# L6472V1.net
KiCad netlist of a schematic drawn in EAGLE
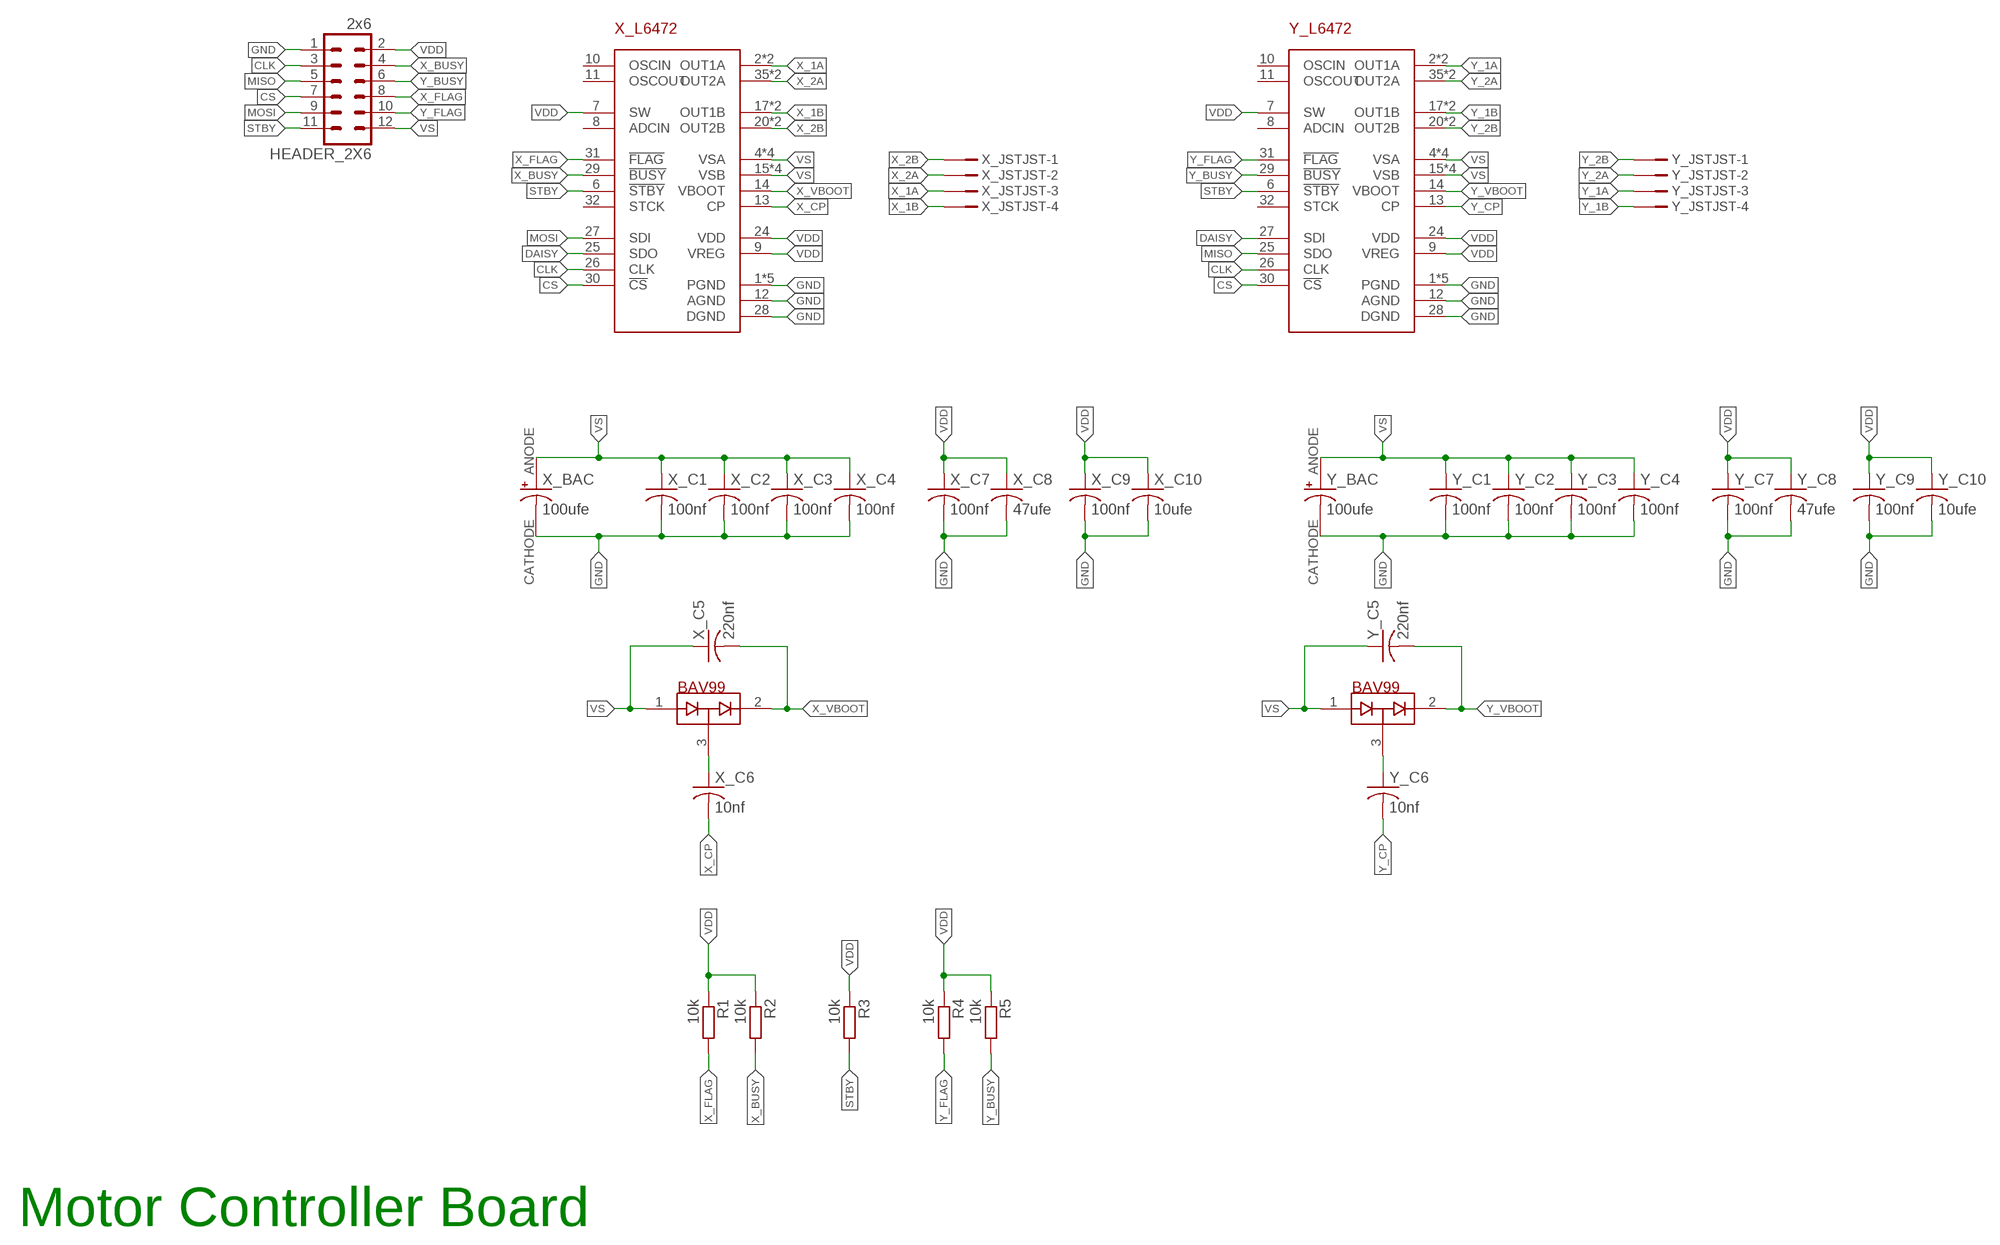
[diagram p0: schematic, sheet 1]

(export (version "E")
  (design (tool "Eeschema 10.0.6"))
  (components
    (comp (ref "HEADER_2X6")
      (value "2x6")
      (footprint "eagle-import:MA06-2")
      (libsource (lib "eagle-import") (part "MA06-2"))
    )
    (comp (ref "R1")
      (value "10k")
      (footprint "eagle-import:M1206")
      (libsource (lib "eagle-import") (part "R-EU_M1206"))
    )
    (comp (ref "R2")
      (value "10k")
      (footprint "eagle-import:M1206")
      (libsource (lib "eagle-import") (part "R-EU_M1206"))
    )
    (comp (ref "R3")
      (value "10k")
      (footprint "eagle-import:M1206")
      (libsource (lib "eagle-import") (part "R-EU_M1206"))
    )
    (comp (ref "R4")
      (value "10k")
      (footprint "eagle-import:M1206")
      (libsource (lib "eagle-import") (part "R-EU_M1206"))
    )
    (comp (ref "R5")
      (value "10k")
      (footprint "eagle-import:M1206")
      (libsource (lib "eagle-import") (part "R-EU_M1206"))
    )
    (comp (ref "X_BAC")
      (value "100ufe")
      (footprint "eagle-import:EEE1AA101WR")
      (libsource (lib "eagle-import") (part "EEE-1AA101WR"))
    )
    (comp (ref "X_BAV99")
      (value "BAV99")
      (footprint "eagle-import:SOT23_CPL")
      (libsource (lib "eagle-import") (part "BAV99"))
    )
    (comp (ref "X_C1")
      (value "100nf")
      (footprint "eagle-import:C1206")
      (libsource (lib "eagle-import") (part "C-USC1206"))
    )
    (comp (ref "X_C2")
      (value "100nf")
      (footprint "eagle-import:C1206")
      (libsource (lib "eagle-import") (part "C-USC1206"))
    )
    (comp (ref "X_C3")
      (value "100nf")
      (footprint "eagle-import:C1206")
      (libsource (lib "eagle-import") (part "C-USC1206"))
    )
    (comp (ref "X_C4")
      (value "100nf")
      (footprint "eagle-import:C1206")
      (libsource (lib "eagle-import") (part "C-USC1206"))
    )
    (comp (ref "X_C5")
      (value "220nf")
      (footprint "eagle-import:C1206")
      (libsource (lib "eagle-import") (part "C-USC1206"))
    )
    (comp (ref "X_C6")
      (value "10nf")
      (footprint "eagle-import:C1206")
      (libsource (lib "eagle-import") (part "C-USC1206"))
    )
    (comp (ref "X_C7")
      (value "100nf")
      (footprint "eagle-import:C1206")
      (libsource (lib "eagle-import") (part "C-USC1206"))
    )
    (comp (ref "X_C8")
      (value "47ufe")
      (footprint "eagle-import:C1206")
      (libsource (lib "eagle-import") (part "C-USC1206"))
    )
    (comp (ref "X_C9")
      (value "100nf")
      (footprint "eagle-import:C1206")
      (libsource (lib "eagle-import") (part "C-USC1206"))
    )
    (comp (ref "X_C10")
      (value "10ufe")
      (footprint "eagle-import:C1206")
      (libsource (lib "eagle-import") (part "C-USC1206"))
    )
    (comp (ref "X_JST")
      (value "JST")
      (footprint "eagle-import:JST-4")
      (libsource (lib "eagle-import") (part "JST"))
    )
    (comp (ref "X_L6472")
      (value "L6472")
      (footprint "eagle-import:PSO36")
      (libsource (lib "eagle-import") (part "L6472"))
    )
    (comp (ref "Y_BAC")
      (value "100ufe")
      (footprint "eagle-import:EEE1AA101WR")
      (libsource (lib "eagle-import") (part "EEE-1AA101WR"))
    )
    (comp (ref "Y_BAV99")
      (value "BAV99")
      (footprint "eagle-import:SOT23_CPL")
      (libsource (lib "eagle-import") (part "BAV99"))
    )
    (comp (ref "Y_C1")
      (value "100nf")
      (footprint "eagle-import:C1206")
      (libsource (lib "eagle-import") (part "C-USC1206"))
    )
    (comp (ref "Y_C2")
      (value "100nf")
      (footprint "eagle-import:C1206")
      (libsource (lib "eagle-import") (part "C-USC1206"))
    )
    (comp (ref "Y_C3")
      (value "100nf")
      (footprint "eagle-import:C1206")
      (libsource (lib "eagle-import") (part "C-USC1206"))
    )
    (comp (ref "Y_C4")
      (value "100nf")
      (footprint "eagle-import:C1206")
      (libsource (lib "eagle-import") (part "C-USC1206"))
    )
    (comp (ref "Y_C5")
      (value "220nf")
      (footprint "eagle-import:C1206")
      (libsource (lib "eagle-import") (part "C-USC1206"))
    )
    (comp (ref "Y_C6")
      (value "10nf")
      (footprint "eagle-import:C1206")
      (libsource (lib "eagle-import") (part "C-USC1206"))
    )
    (comp (ref "Y_C7")
      (value "100nf")
      (footprint "eagle-import:C1206")
      (libsource (lib "eagle-import") (part "C-USC1206"))
    )
    (comp (ref "Y_C8")
      (value "47ufe")
      (footprint "eagle-import:C1206")
      (libsource (lib "eagle-import") (part "C-USC1206"))
    )
    (comp (ref "Y_C9")
      (value "100nf")
      (footprint "eagle-import:C1206")
      (libsource (lib "eagle-import") (part "C-USC1206"))
    )
    (comp (ref "Y_C10")
      (value "10ufe")
      (footprint "eagle-import:C1206")
      (libsource (lib "eagle-import") (part "C-USC1206"))
    )
    (comp (ref "Y_JST")
      (value "JST")
      (footprint "eagle-import:JST-4")
      (libsource (lib "eagle-import") (part "JST"))
    )
    (comp (ref "Y_L6472")
      (value "L6472")
      (footprint "eagle-import:PSO36")
      (libsource (lib "eagle-import") (part "L6472"))
    )
  )
  (nets
    (net (code "1") (name "CLK") (class "Default")
      (node (ref "HEADER_2X6") (pin "3") (pinfunction "3_3") (pintype "passive"))
      (node (ref "X_L6472") (pin "26") (pinfunction "CLK_26") (pintype "bidirectional"))
      (node (ref "Y_L6472") (pin "26") (pinfunction "CLK_26") (pintype "bidirectional"))
    )
    (net (code "2") (name "CS") (class "Default")
      (node (ref "HEADER_2X6") (pin "7") (pinfunction "7_7") (pintype "passive"))
      (node (ref "X_L6472") (pin "30") (pinfunction "~{CS}_30") (pintype "bidirectional"))
      (node (ref "Y_L6472") (pin "30") (pinfunction "~{CS}_30") (pintype "bidirectional"))
    )
    (net (code "3") (name "DAISY") (class "Default")
      (node (ref "X_L6472") (pin "25") (pinfunction "SDO_25") (pintype "bidirectional"))
      (node (ref "Y_L6472") (pin "27") (pinfunction "SDI_27") (pintype "bidirectional"))
    )
    (net (code "4") (name "GND") (class "Default")
      (node (ref "HEADER_2X6") (pin "1") (pinfunction "1_1") (pintype "passive"))
      (node (ref "X_BAC") (pin "CATHODE") (pinfunction "-_CATHODE") (pintype "passive"))
      (node (ref "X_C1") (pin "2") (pinfunction "2_2") (pintype "passive"))
      (node (ref "X_C10") (pin "2") (pinfunction "2_2") (pintype "passive"))
      (node (ref "X_C2") (pin "2") (pinfunction "2_2") (pintype "passive"))
      (node (ref "X_C3") (pin "2") (pinfunction "2_2") (pintype "passive"))
      (node (ref "X_C4") (pin "2") (pinfunction "2_2") (pintype "passive"))
      (node (ref "X_C7") (pin "2") (pinfunction "2_2") (pintype "passive"))
      (node (ref "X_C8") (pin "2") (pinfunction "2_2") (pintype "passive"))
      (node (ref "X_C9") (pin "2") (pinfunction "2_2") (pintype "passive"))
      (node (ref "X_L6472") (pin "1") (pinfunction "PGND_1") (pintype "bidirectional"))
      (node (ref "X_L6472") (pin "12") (pinfunction "AGND_12") (pintype "bidirectional"))
      (node (ref "X_L6472") (pin "19") (pinfunction "PGND_19") (pintype "bidirectional"))
      (node (ref "X_L6472") (pin "28") (pinfunction "DGND_28") (pintype "bidirectional"))
      (node (ref "X_L6472") (pin "M@1") (pinfunction "PGND_M@1") (pintype "bidirectional"))
      (node (ref "X_L6472") (pin "M@2") (pinfunction "PGND_M@2") (pintype "bidirectional"))
      (node (ref "X_L6472") (pin "M@3") (pinfunction "PGND_M@3") (pintype "bidirectional"))
      (node (ref "Y_BAC") (pin "CATHODE") (pinfunction "-_CATHODE") (pintype "passive"))
      (node (ref "Y_C1") (pin "2") (pinfunction "2_2") (pintype "passive"))
      (node (ref "Y_C10") (pin "2") (pinfunction "2_2") (pintype "passive"))
      (node (ref "Y_C2") (pin "2") (pinfunction "2_2") (pintype "passive"))
      (node (ref "Y_C3") (pin "2") (pinfunction "2_2") (pintype "passive"))
      (node (ref "Y_C4") (pin "2") (pinfunction "2_2") (pintype "passive"))
      (node (ref "Y_C7") (pin "2") (pinfunction "2_2") (pintype "passive"))
      (node (ref "Y_C8") (pin "2") (pinfunction "2_2") (pintype "passive"))
      (node (ref "Y_C9") (pin "2") (pinfunction "2_2") (pintype "passive"))
      (node (ref "Y_L6472") (pin "1") (pinfunction "PGND_1") (pintype "bidirectional"))
      (node (ref "Y_L6472") (pin "12") (pinfunction "AGND_12") (pintype "bidirectional"))
      (node (ref "Y_L6472") (pin "19") (pinfunction "PGND_19") (pintype "bidirectional"))
      (node (ref "Y_L6472") (pin "28") (pinfunction "DGND_28") (pintype "bidirectional"))
      (node (ref "Y_L6472") (pin "M@1") (pinfunction "PGND_M@1") (pintype "bidirectional"))
      (node (ref "Y_L6472") (pin "M@2") (pinfunction "PGND_M@2") (pintype "bidirectional"))
      (node (ref "Y_L6472") (pin "M@3") (pinfunction "PGND_M@3") (pintype "bidirectional"))
    )
    (net (code "5") (name "MISO") (class "Default")
      (node (ref "HEADER_2X6") (pin "5") (pinfunction "5_5") (pintype "passive"))
      (node (ref "Y_L6472") (pin "25") (pinfunction "SDO_25") (pintype "bidirectional"))
    )
    (net (code "6") (name "MOSI") (class "Default")
      (node (ref "HEADER_2X6") (pin "9") (pinfunction "9_9") (pintype "passive"))
      (node (ref "X_L6472") (pin "27") (pinfunction "SDI_27") (pintype "bidirectional"))
    )
    (net (code "7") (name "Net-(X_BAV99-COM)") (class "Default")
      (node (ref "X_BAV99") (pin "3") (pinfunction "COM_3") (pintype "bidirectional"))
      (node (ref "X_C6") (pin "1") (pinfunction "1_1") (pintype "passive"))
    )
    (net (code "8") (name "Net-(Y_BAV99-COM)") (class "Default")
      (node (ref "Y_BAV99") (pin "3") (pinfunction "COM_3") (pintype "bidirectional"))
      (node (ref "Y_C6") (pin "1") (pinfunction "1_1") (pintype "passive"))
    )
    (net (code "9") (name "STBY") (class "Default")
      (node (ref "HEADER_2X6") (pin "11") (pinfunction "11_11") (pintype "passive"))
      (node (ref "R3") (pin "2") (pinfunction "2_2") (pintype "passive"))
      (node (ref "X_L6472") (pin "6") (pinfunction "~{STBY}_6") (pintype "bidirectional"))
      (node (ref "Y_L6472") (pin "6") (pinfunction "~{STBY}_6") (pintype "bidirectional"))
    )
    (net (code "10") (name "VDD") (class "Default")
      (node (ref "HEADER_2X6") (pin "2") (pinfunction "2_2") (pintype "passive"))
      (node (ref "R1") (pin "1") (pinfunction "1_1") (pintype "passive"))
      (node (ref "R2") (pin "1") (pinfunction "1_1") (pintype "passive"))
      (node (ref "R3") (pin "1") (pinfunction "1_1") (pintype "passive"))
      (node (ref "R4") (pin "1") (pinfunction "1_1") (pintype "passive"))
      (node (ref "R5") (pin "1") (pinfunction "1_1") (pintype "passive"))
      (node (ref "X_C10") (pin "1") (pinfunction "1_1") (pintype "passive"))
      (node (ref "X_C7") (pin "1") (pinfunction "1_1") (pintype "passive"))
      (node (ref "X_C8") (pin "1") (pinfunction "1_1") (pintype "passive"))
      (node (ref "X_C9") (pin "1") (pinfunction "1_1") (pintype "passive"))
      (node (ref "X_L6472") (pin "24") (pinfunction "VDD_24") (pintype "bidirectional"))
      (node (ref "X_L6472") (pin "7") (pinfunction "SW_7") (pintype "bidirectional"))
      (node (ref "X_L6472") (pin "9") (pinfunction "VREG_9") (pintype "bidirectional"))
      (node (ref "Y_C10") (pin "1") (pinfunction "1_1") (pintype "passive"))
      (node (ref "Y_C7") (pin "1") (pinfunction "1_1") (pintype "passive"))
      (node (ref "Y_C8") (pin "1") (pinfunction "1_1") (pintype "passive"))
      (node (ref "Y_C9") (pin "1") (pinfunction "1_1") (pintype "passive"))
      (node (ref "Y_L6472") (pin "24") (pinfunction "VDD_24") (pintype "bidirectional"))
      (node (ref "Y_L6472") (pin "7") (pinfunction "SW_7") (pintype "bidirectional"))
      (node (ref "Y_L6472") (pin "9") (pinfunction "VREG_9") (pintype "bidirectional"))
    )
    (net (code "11") (name "VS") (class "Default")
      (node (ref "HEADER_2X6") (pin "12") (pinfunction "12_12") (pintype "passive"))
      (node (ref "X_BAC") (pin "ANODE") (pinfunction "+_ANODE") (pintype "passive"))
      (node (ref "X_BAV99") (pin "1") (pinfunction "A1_1") (pintype "bidirectional"))
      (node (ref "X_C1") (pin "1") (pinfunction "1_1") (pintype "passive"))
      (node (ref "X_C2") (pin "1") (pinfunction "1_1") (pintype "passive"))
      (node (ref "X_C3") (pin "1") (pinfunction "1_1") (pintype "passive"))
      (node (ref "X_C4") (pin "1") (pinfunction "1_1") (pintype "passive"))
      (node (ref "X_C5") (pin "1") (pinfunction "1_1") (pintype "passive"))
      (node (ref "X_L6472") (pin "15") (pinfunction "VSB_15") (pintype "bidirectional"))
      (node (ref "X_L6472") (pin "16") (pinfunction "VSB_16") (pintype "bidirectional"))
      (node (ref "X_L6472") (pin "22") (pinfunction "VSB_22") (pintype "bidirectional"))
      (node (ref "X_L6472") (pin "23") (pinfunction "VSB_23") (pintype "bidirectional"))
      (node (ref "X_L6472") (pin "33") (pinfunction "VSA_33") (pintype "bidirectional"))
      (node (ref "X_L6472") (pin "34") (pinfunction "VSA_34") (pintype "bidirectional"))
      (node (ref "X_L6472") (pin "4") (pinfunction "VSA_4") (pintype "bidirectional"))
      (node (ref "X_L6472") (pin "5") (pinfunction "VSA_5") (pintype "bidirectional"))
      (node (ref "Y_BAC") (pin "ANODE") (pinfunction "+_ANODE") (pintype "passive"))
      (node (ref "Y_BAV99") (pin "1") (pinfunction "A1_1") (pintype "bidirectional"))
      (node (ref "Y_C1") (pin "1") (pinfunction "1_1") (pintype "passive"))
      (node (ref "Y_C2") (pin "1") (pinfunction "1_1") (pintype "passive"))
      (node (ref "Y_C3") (pin "1") (pinfunction "1_1") (pintype "passive"))
      (node (ref "Y_C4") (pin "1") (pinfunction "1_1") (pintype "passive"))
      (node (ref "Y_C5") (pin "1") (pinfunction "1_1") (pintype "passive"))
      (node (ref "Y_L6472") (pin "15") (pinfunction "VSB_15") (pintype "bidirectional"))
      (node (ref "Y_L6472") (pin "16") (pinfunction "VSB_16") (pintype "bidirectional"))
      (node (ref "Y_L6472") (pin "22") (pinfunction "VSB_22") (pintype "bidirectional"))
      (node (ref "Y_L6472") (pin "23") (pinfunction "VSB_23") (pintype "bidirectional"))
      (node (ref "Y_L6472") (pin "33") (pinfunction "VSA_33") (pintype "bidirectional"))
      (node (ref "Y_L6472") (pin "34") (pinfunction "VSA_34") (pintype "bidirectional"))
      (node (ref "Y_L6472") (pin "4") (pinfunction "VSA_4") (pintype "bidirectional"))
      (node (ref "Y_L6472") (pin "5") (pinfunction "VSA_5") (pintype "bidirectional"))
    )
    (net (code "12") (name "X_1A") (class "Default")
      (node (ref "X_JST") (pin "P2") (pinfunction "1_P2") (pintype "passive"))
      (node (ref "X_L6472") (pin "2") (pinfunction "OUT1A_2") (pintype "bidirectional"))
      (node (ref "X_L6472") (pin "3") (pinfunction "OUT1A_3") (pintype "bidirectional"))
    )
    (net (code "13") (name "X_1B") (class "Default")
      (node (ref "X_JST") (pin "P3") (pinfunction "1_P3") (pintype "passive"))
      (node (ref "X_L6472") (pin "17") (pinfunction "OUT1B_17") (pintype "bidirectional"))
      (node (ref "X_L6472") (pin "18") (pinfunction "OUT1B_18") (pintype "bidirectional"))
    )
    (net (code "14") (name "X_2A") (class "Default")
      (node (ref "X_JST") (pin "P1") (pinfunction "1_P1") (pintype "passive"))
      (node (ref "X_L6472") (pin "35") (pinfunction "OUT2A_35") (pintype "bidirectional"))
      (node (ref "X_L6472") (pin "36") (pinfunction "OUT2A_36") (pintype "bidirectional"))
    )
    (net (code "15") (name "X_2B") (class "Default")
      (node (ref "X_JST") (pin "P0") (pinfunction "1_P0") (pintype "passive"))
      (node (ref "X_L6472") (pin "20") (pinfunction "OUT2B_20") (pintype "bidirectional"))
      (node (ref "X_L6472") (pin "21") (pinfunction "OUT2B_21") (pintype "bidirectional"))
    )
    (net (code "16") (name "X_BUSY") (class "Default")
      (node (ref "HEADER_2X6") (pin "4") (pinfunction "4_4") (pintype "passive"))
      (node (ref "R2") (pin "2") (pinfunction "2_2") (pintype "passive"))
      (node (ref "X_L6472") (pin "29") (pinfunction "~{BUSY}_29") (pintype "bidirectional"))
    )
    (net (code "17") (name "X_CP") (class "Default")
      (node (ref "X_C6") (pin "2") (pinfunction "2_2") (pintype "passive"))
      (node (ref "X_L6472") (pin "13") (pinfunction "CP_13") (pintype "bidirectional"))
    )
    (net (code "18") (name "X_FLAG") (class "Default")
      (node (ref "HEADER_2X6") (pin "8") (pinfunction "8_8") (pintype "passive"))
      (node (ref "R1") (pin "2") (pinfunction "2_2") (pintype "passive"))
      (node (ref "X_L6472") (pin "31") (pinfunction "~{FLAG}_31") (pintype "bidirectional"))
    )
    (net (code "19") (name "X_VBOOT") (class "Default")
      (node (ref "X_BAV99") (pin "2") (pinfunction "C2_2") (pintype "bidirectional"))
      (node (ref "X_C5") (pin "2") (pinfunction "2_2") (pintype "passive"))
      (node (ref "X_L6472") (pin "14") (pinfunction "VBOOT_14") (pintype "bidirectional"))
    )
    (net (code "20") (name "Y_1A") (class "Default")
      (node (ref "Y_JST") (pin "P2") (pinfunction "1_P2") (pintype "passive"))
      (node (ref "Y_L6472") (pin "2") (pinfunction "OUT1A_2") (pintype "bidirectional"))
      (node (ref "Y_L6472") (pin "3") (pinfunction "OUT1A_3") (pintype "bidirectional"))
    )
    (net (code "21") (name "Y_1B") (class "Default")
      (node (ref "Y_JST") (pin "P3") (pinfunction "1_P3") (pintype "passive"))
      (node (ref "Y_L6472") (pin "17") (pinfunction "OUT1B_17") (pintype "bidirectional"))
      (node (ref "Y_L6472") (pin "18") (pinfunction "OUT1B_18") (pintype "bidirectional"))
    )
    (net (code "22") (name "Y_2A") (class "Default")
      (node (ref "Y_JST") (pin "P1") (pinfunction "1_P1") (pintype "passive"))
      (node (ref "Y_L6472") (pin "35") (pinfunction "OUT2A_35") (pintype "bidirectional"))
      (node (ref "Y_L6472") (pin "36") (pinfunction "OUT2A_36") (pintype "bidirectional"))
    )
    (net (code "23") (name "Y_2B") (class "Default")
      (node (ref "Y_JST") (pin "P0") (pinfunction "1_P0") (pintype "passive"))
      (node (ref "Y_L6472") (pin "20") (pinfunction "OUT2B_20") (pintype "bidirectional"))
      (node (ref "Y_L6472") (pin "21") (pinfunction "OUT2B_21") (pintype "bidirectional"))
    )
    (net (code "24") (name "Y_BUSY") (class "Default")
      (node (ref "HEADER_2X6") (pin "6") (pinfunction "6_6") (pintype "passive"))
      (node (ref "R5") (pin "2") (pinfunction "2_2") (pintype "passive"))
      (node (ref "Y_L6472") (pin "29") (pinfunction "~{BUSY}_29") (pintype "bidirectional"))
    )
    (net (code "25") (name "Y_CP") (class "Default")
      (node (ref "Y_C6") (pin "2") (pinfunction "2_2") (pintype "passive"))
      (node (ref "Y_L6472") (pin "13") (pinfunction "CP_13") (pintype "bidirectional"))
    )
    (net (code "26") (name "Y_FLAG") (class "Default")
      (node (ref "HEADER_2X6") (pin "10") (pinfunction "10_10") (pintype "passive"))
      (node (ref "R4") (pin "2") (pinfunction "2_2") (pintype "passive"))
      (node (ref "Y_L6472") (pin "31") (pinfunction "~{FLAG}_31") (pintype "bidirectional"))
    )
    (net (code "27") (name "Y_VBOOT") (class "Default")
      (node (ref "Y_BAV99") (pin "2") (pinfunction "C2_2") (pintype "bidirectional"))
      (node (ref "Y_C5") (pin "2") (pinfunction "2_2") (pintype "passive"))
      (node (ref "Y_L6472") (pin "14") (pinfunction "VBOOT_14") (pintype "bidirectional"))
    )
    (net (code "28") (name "unconnected-(X_L6472-ADCIN-Pad8)") (class "Default")
      (node (ref "X_L6472") (pin "8") (pinfunction "ADCIN_8") (pintype "bidirectional"))
    )
    (net (code "29") (name "unconnected-(X_L6472-OSCIN-Pad10)") (class "Default")
      (node (ref "X_L6472") (pin "10") (pinfunction "OSCIN_10") (pintype "bidirectional"))
    )
    (net (code "30") (name "unconnected-(X_L6472-OSCOUT-Pad11)") (class "Default")
      (node (ref "X_L6472") (pin "11") (pinfunction "OSCOUT_11") (pintype "bidirectional"))
    )
    (net (code "31") (name "unconnected-(X_L6472-STCK-Pad32)") (class "Default")
      (node (ref "X_L6472") (pin "32") (pinfunction "STCK_32") (pintype "bidirectional"))
    )
    (net (code "32") (name "unconnected-(Y_L6472-ADCIN-Pad8)") (class "Default")
      (node (ref "Y_L6472") (pin "8") (pinfunction "ADCIN_8") (pintype "bidirectional"))
    )
    (net (code "33") (name "unconnected-(Y_L6472-OSCIN-Pad10)") (class "Default")
      (node (ref "Y_L6472") (pin "10") (pinfunction "OSCIN_10") (pintype "bidirectional"))
    )
    (net (code "34") (name "unconnected-(Y_L6472-OSCOUT-Pad11)") (class "Default")
      (node (ref "Y_L6472") (pin "11") (pinfunction "OSCOUT_11") (pintype "bidirectional"))
    )
    (net (code "35") (name "unconnected-(Y_L6472-STCK-Pad32)") (class "Default")
      (node (ref "Y_L6472") (pin "32") (pinfunction "STCK_32") (pintype "bidirectional"))
    )
  )
)
